# CMWC-Product.net
KiCad netlist of a schematic drawn in EAGLE
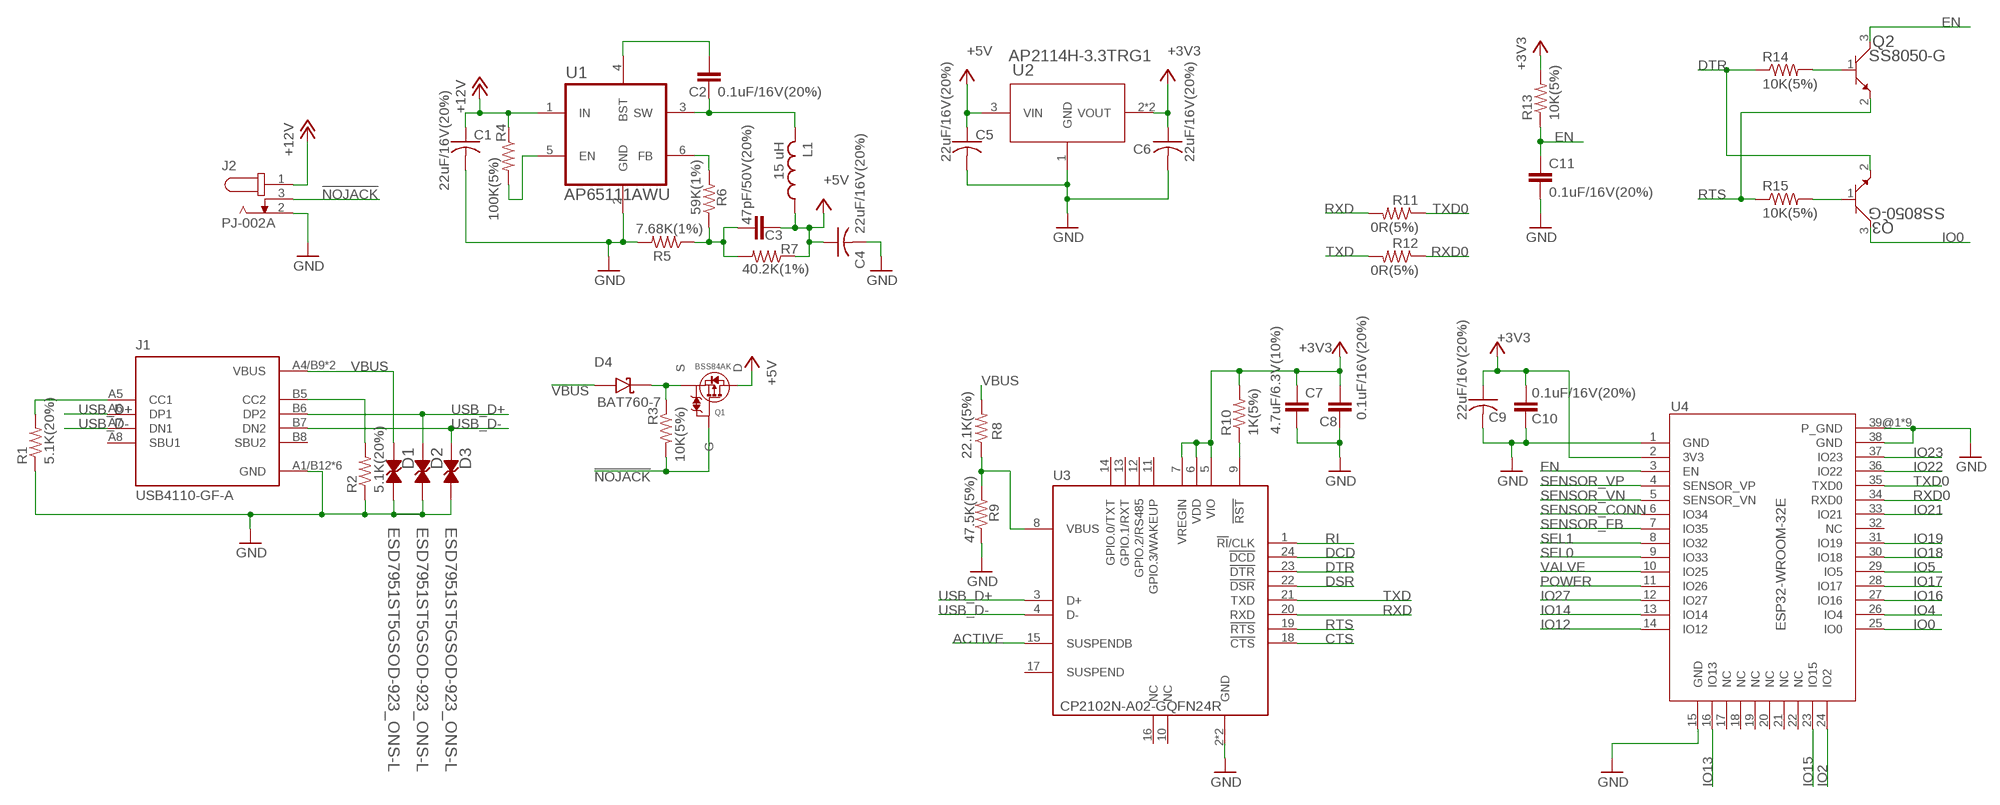
[diagram p0: schematic, sheet 1, part 1 of 2]
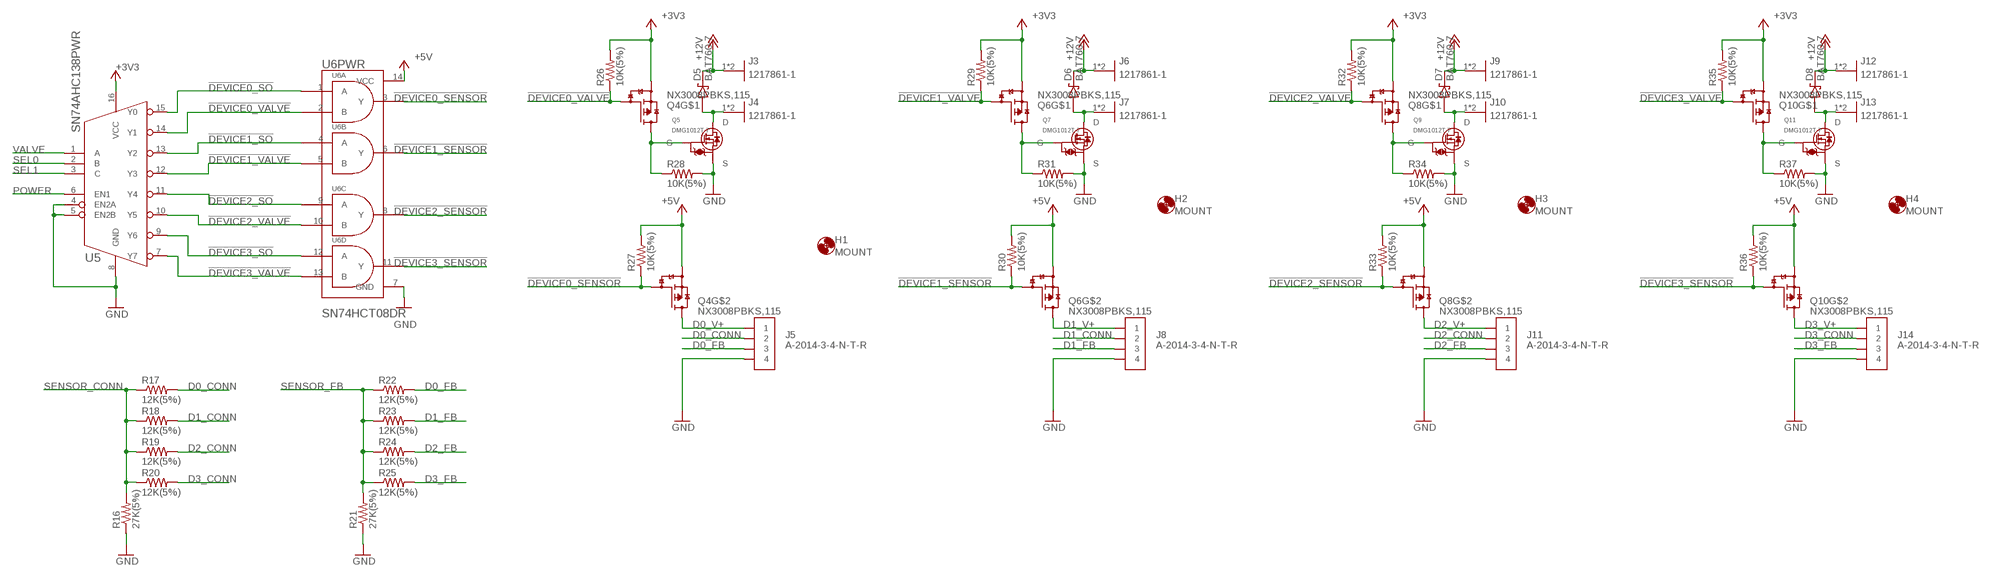
[diagram p1: schematic, sheet 1, part 2 of 2]

(export (version "E")
  (design (tool "Eeschema 10.0.6"))
  (components
    (comp (ref "C1")
      (value "22uF/16V(20%)")
      (footprint "eagle-import:C1206")
      (fields (field (name "DIGI-KEY_PART_NUMBER") "1276-2728-1-ND"))
      (libsource (lib "eagle-import") (part "C-USC1206"))
    )
    (comp (ref "C2")
      (value "0.1uF/16V(20%)")
      (footprint "eagle-import:C0603")
      (fields (field (name "DIGI-KEY_PART_NUMBER") "399-1099-1-ND"))
      (libsource (lib "eagle-import") (part "C-EUC0603"))
    )
    (comp (ref "C3")
      (value "47pF/50V(20%)")
      (footprint "eagle-import:C0603")
      (fields (field (name "DIGI-KEY_PART_NUMBER") "399-1099-1-ND"))
      (libsource (lib "eagle-import") (part "C-EUC0603"))
    )
    (comp (ref "C4")
      (value "22uF/16V(20%)")
      (footprint "eagle-import:C1206")
      (fields (field (name "DIGI-KEY_PART_NUMBER") "1276-2728-1-ND"))
      (libsource (lib "eagle-import") (part "C-USC1206"))
    )
    (comp (ref "C5")
      (value "22uF/16V(20%)")
      (footprint "eagle-import:C1206")
      (fields (field (name "DIGI-KEY_PART_NUMBER") "1276-2728-1-ND"))
      (libsource (lib "eagle-import") (part "C-USC1206"))
    )
    (comp (ref "C6")
      (value "22uF/16V(20%)")
      (footprint "eagle-import:C1206")
      (fields (field (name "DIGI-KEY_PART_NUMBER") "1276-2728-1-ND"))
      (libsource (lib "eagle-import") (part "C-USC1206"))
    )
    (comp (ref "C7")
      (value "4.7uF/6.3V(10%)")
      (footprint "eagle-import:C0603")
      (fields (field (name "DIGI-KEY_PART_NUMBER") "1276-1045-1-ND"))
      (libsource (lib "eagle-import") (part "C-EUC0603"))
    )
    (comp (ref "C8")
      (value "0.1uF/16V(20%)")
      (footprint "eagle-import:C0603")
      (fields (field (name "DIGI-KEY_PART_NUMBER") "399-1099-1-ND"))
      (libsource (lib "eagle-import") (part "C-EUC0603"))
    )
    (comp (ref "C9")
      (value "22uF/16V(20%)")
      (footprint "eagle-import:C1206")
      (fields (field (name "DIGI-KEY_PART_NUMBER") "1276-2728-1-ND"))
      (libsource (lib "eagle-import") (part "C-USC1206"))
    )
    (comp (ref "C10")
      (value "0.1uF/16V(20%)")
      (footprint "eagle-import:C0603")
      (fields (field (name "DIGI-KEY_PART_NUMBER") "399-1099-1-ND"))
      (libsource (lib "eagle-import") (part "C-EUC0603"))
    )
    (comp (ref "C11")
      (value "0.1uF/16V(20%)")
      (footprint "eagle-import:C0603")
      (fields (field (name "DIGI-KEY_PART_NUMBER") "399-1099-1-ND"))
      (libsource (lib "eagle-import") (part "C-EUC0603"))
    )
    (comp (ref "D1")
      (value "ESD7951ST5GSOD-923_ONS-L")
      (footprint "eagle-import:SOD-923_ONS-L")
      (fields
        (field (name "DIGI-KEY_PART_NUMBER") "ESD7951ST5GOSCT-ND")
        (field (name "MANUFACTURER_PART_NUMBER") "ESD7951ST5G")
        (field (name "COPYRIGHT") "Copyright (C) 2018 Accelerated Designs. All rights reserved")
      )
      (libsource (lib "eagle-import") (part "ESD7951ST5GSOD-923_ONS-L"))
    )
    (comp (ref "D2")
      (value "ESD7951ST5GSOD-923_ONS-L")
      (footprint "eagle-import:SOD-923_ONS-L")
      (fields
        (field (name "DIGI-KEY_PART_NUMBER") "ESD7951ST5GOSCT-ND")
        (field (name "MANUFACTURER_PART_NUMBER") "ESD7951ST5G")
        (field (name "COPYRIGHT") "Copyright (C) 2018 Accelerated Designs. All rights reserved")
      )
      (libsource (lib "eagle-import") (part "ESD7951ST5GSOD-923_ONS-L"))
    )
    (comp (ref "D3")
      (value "ESD7951ST5GSOD-923_ONS-L")
      (footprint "eagle-import:SOD-923_ONS-L")
      (fields
        (field (name "DIGI-KEY_PART_NUMBER") "ESD7951ST5GOSCT-ND")
        (field (name "MANUFACTURER_PART_NUMBER") "ESD7951ST5G")
        (field (name "COPYRIGHT") "Copyright (C) 2018 Accelerated Designs. All rights reserved")
      )
      (libsource (lib "eagle-import") (part "ESD7951ST5GSOD-923_ONS-L"))
    )
    (comp (ref "D4")
      (value "BAT760-7")
      (footprint "eagle-import:SOD2513X120N")
      (fields (field (name "DIGI-KEY_PART_NUMBER") "BAT760DICT-ND") (field (name "MF") "Diodes Inc."))
      (libsource (lib "eagle-import") (part "BAT760-7"))
    )
    (comp (ref "D5")
      (value "BAT760-7")
      (footprint "eagle-import:SOD2513X120N")
      (fields (field (name "DIGI-KEY_PART_NUMBER") "BAT760DICT-ND") (field (name "MF") "Diodes Inc."))
      (libsource (lib "eagle-import") (part "BAT760-7"))
    )
    (comp (ref "D6")
      (value "BAT760-7")
      (footprint "eagle-import:SOD2513X120N")
      (fields (field (name "DIGI-KEY_PART_NUMBER") "BAT760DICT-ND") (field (name "MF") "Diodes Inc."))
      (libsource (lib "eagle-import") (part "BAT760-7"))
    )
    (comp (ref "D7")
      (value "BAT760-7")
      (footprint "eagle-import:SOD2513X120N")
      (fields (field (name "DIGI-KEY_PART_NUMBER") "BAT760DICT-ND") (field (name "MF") "Diodes Inc."))
      (libsource (lib "eagle-import") (part "BAT760-7"))
    )
    (comp (ref "D8")
      (value "BAT760-7")
      (footprint "eagle-import:SOD2513X120N")
      (fields (field (name "DIGI-KEY_PART_NUMBER") "BAT760DICT-ND") (field (name "MF") "Diodes Inc."))
      (libsource (lib "eagle-import") (part "BAT760-7"))
    )
    (comp (ref "H1")
      (value "MOUNT")
      (footprint "eagle-import:#6-MOUNT")
      (libsource (lib "eagle-import") (part "MOUNT"))
    )
    (comp (ref "H2")
      (value "MOUNT")
      (footprint "eagle-import:#6-MOUNT")
      (libsource (lib "eagle-import") (part "MOUNT"))
    )
    (comp (ref "H3")
      (value "MOUNT")
      (footprint "eagle-import:#6-MOUNT")
      (libsource (lib "eagle-import") (part "MOUNT"))
    )
    (comp (ref "H4")
      (value "MOUNT")
      (footprint "eagle-import:#6-MOUNT")
      (libsource (lib "eagle-import") (part "MOUNT"))
    )
    (comp (ref "J1")
      (value "USB4110-GF-A")
      (footprint "eagle-import:GCT_USB4110-GF-A")
      (fields (field (name "DIGI-KEY_PART_NUMBER") "2073-USB4110-GF-A-1-ND") (field (name "MF") "GCT"))
      (libsource (lib "eagle-import") (part "USB4110-GF-A"))
    )
    (comp (ref "J2")
      (value "PJ-002A")
      (footprint "eagle-import:CUI_PJ-002A")
      (fields (field (name "DIGI-KEY_PART_NUMBER") "CP-002A-ND") (field (name "MF") "CUI Devices"))
      (libsource (lib "eagle-import") (part "PJ-002A"))
    )
    (comp (ref "J3")
      (value "1217861-1")
      (footprint "eagle-import:TE_1217861-1")
      (fields (field (name "DIGI-KEY_PART_NUMBER") "A100452CT-ND") (field (name "MF") "TE Connectivity"))
      (libsource (lib "eagle-import") (part "1217861-1"))
    )
    (comp (ref "J4")
      (value "1217861-1")
      (footprint "eagle-import:TE_1217861-1")
      (fields (field (name "DIGI-KEY_PART_NUMBER") "A100452CT-ND") (field (name "MF") "TE Connectivity"))
      (libsource (lib "eagle-import") (part "1217861-1"))
    )
    (comp (ref "J5")
      (value "A-2014-3-4-N-T-R")
      (footprint "eagle-import:A-2014-3-4-N-T-R")
      (fields (field (name "DIGI-KEY_PART_NUMBER") "AE10393-ND"))
      (libsource (lib "eagle-import") (part "A-2014-3-4-N-T-R"))
    )
    (comp (ref "J6")
      (value "1217861-1")
      (footprint "eagle-import:TE_1217861-1")
      (fields (field (name "DIGI-KEY_PART_NUMBER") "A100452CT-ND") (field (name "MF") "TE Connectivity"))
      (libsource (lib "eagle-import") (part "1217861-1"))
    )
    (comp (ref "J7")
      (value "1217861-1")
      (footprint "eagle-import:TE_1217861-1")
      (fields (field (name "DIGI-KEY_PART_NUMBER") "A100452CT-ND") (field (name "MF") "TE Connectivity"))
      (libsource (lib "eagle-import") (part "1217861-1"))
    )
    (comp (ref "J8")
      (value "A-2014-3-4-N-T-R")
      (footprint "eagle-import:A-2014-3-4-N-T-R")
      (fields (field (name "DIGI-KEY_PART_NUMBER") "AE10393-ND"))
      (libsource (lib "eagle-import") (part "A-2014-3-4-N-T-R"))
    )
    (comp (ref "J9")
      (value "1217861-1")
      (footprint "eagle-import:TE_1217861-1")
      (fields (field (name "DIGI-KEY_PART_NUMBER") "A100452CT-ND") (field (name "MF") "TE Connectivity"))
      (libsource (lib "eagle-import") (part "1217861-1"))
    )
    (comp (ref "J10")
      (value "1217861-1")
      (footprint "eagle-import:TE_1217861-1")
      (fields (field (name "DIGI-KEY_PART_NUMBER") "A100452CT-ND") (field (name "MF") "TE Connectivity"))
      (libsource (lib "eagle-import") (part "1217861-1"))
    )
    (comp (ref "J11")
      (value "A-2014-3-4-N-T-R")
      (footprint "eagle-import:A-2014-3-4-N-T-R")
      (fields (field (name "DIGI-KEY_PART_NUMBER") "AE10393-ND"))
      (libsource (lib "eagle-import") (part "A-2014-3-4-N-T-R"))
    )
    (comp (ref "J12")
      (value "1217861-1")
      (footprint "eagle-import:TE_1217861-1")
      (fields (field (name "DIGI-KEY_PART_NUMBER") "A100452CT-ND") (field (name "MF") "TE Connectivity"))
      (libsource (lib "eagle-import") (part "1217861-1"))
    )
    (comp (ref "J13")
      (value "1217861-1")
      (footprint "eagle-import:TE_1217861-1")
      (fields (field (name "DIGI-KEY_PART_NUMBER") "A100452CT-ND") (field (name "MF") "TE Connectivity"))
      (libsource (lib "eagle-import") (part "1217861-1"))
    )
    (comp (ref "J14")
      (value "A-2014-3-4-N-T-R")
      (footprint "eagle-import:A-2014-3-4-N-T-R")
      (fields (field (name "DIGI-KEY_PART_NUMBER") "AE10393-ND"))
      (libsource (lib "eagle-import") (part "A-2014-3-4-N-T-R"))
    )
    (comp (ref "L1")
      (value "15 uH")
      (footprint "eagle-import:BWVS00505040")
      (fields (field (name "DIGI-KEY_PART_NUMBER") "2184-BWVS00505040150M00CT-ND"))
      (libsource (lib "eagle-import") (part "BWVS00505040150M00"))
    )
    (comp (ref "Q1")
      (value "BSS84AK")
      (footprint "eagle-import:TO236")
      (fields (field (name "DIGI-KEY_PART_NUMBER") "1727-1144-1-ND"))
      (libsource (lib "eagle-import") (part "BSS84AK"))
    )
    (comp (ref "Q2")
      (value "SS8050-G")
      (footprint "eagle-import:TRAN_SS8050-G_CIP")
      (fields
        (field (name "DIGI-KEY_PART_NUMBER") "641-1790-1-ND")
        (field (name "COPYRIGHT") "Copyright (C) 2018 Accelerated Designs. All rights reserved")
      )
      (libsource (lib "eagle-import") (part "SS8050-G"))
    )
    (comp (ref "Q3")
      (value "SS8050-G")
      (footprint "eagle-import:TRAN_SS8050-G_CIP")
      (fields
        (field (name "DIGI-KEY_PART_NUMBER") "641-1790-1-ND")
        (field (name "COPYRIGHT") "Copyright (C) 2018 Accelerated Designs. All rights reserved")
      )
      (libsource (lib "eagle-import") (part "SS8050-G"))
    )
    (comp (ref "Q4")
      (value "NX3008PBKS,115")
      (footprint "eagle-import:SOT65P210X110-6N")
      (fields (field (name "DIGI-KEY_PART_NUMBER") "1727-1282-1-ND") (field (name "MF") "Nexperia USA"))
      (libsource (lib "eagle-import") (part "NX3008PBKS,115"))
    )
    (comp (ref "Q5")
      (value "DMG1012T-7")
      (footprint "eagle-import:SOT523")
      (fields (field (name "DIGI-KEY_PART_NUMBER") "DMG1012T-7DICT-ND"))
      (libsource (lib "eagle-import") (part "DMG1012T-7"))
    )
    (comp (ref "Q6")
      (value "NX3008PBKS,115")
      (footprint "eagle-import:SOT65P210X110-6N")
      (fields (field (name "DIGI-KEY_PART_NUMBER") "1727-1282-1-ND") (field (name "MF") "Nexperia USA"))
      (libsource (lib "eagle-import") (part "NX3008PBKS,115"))
    )
    (comp (ref "Q7")
      (value "DMG1012T-7")
      (footprint "eagle-import:SOT523")
      (fields (field (name "DIGI-KEY_PART_NUMBER") "DMG1012T-7DICT-ND"))
      (libsource (lib "eagle-import") (part "DMG1012T-7"))
    )
    (comp (ref "Q8")
      (value "NX3008PBKS,115")
      (footprint "eagle-import:SOT65P210X110-6N")
      (fields (field (name "DIGI-KEY_PART_NUMBER") "1727-1282-1-ND") (field (name "MF") "Nexperia USA"))
      (libsource (lib "eagle-import") (part "NX3008PBKS,115"))
    )
    (comp (ref "Q9")
      (value "DMG1012T-7")
      (footprint "eagle-import:SOT523")
      (fields (field (name "DIGI-KEY_PART_NUMBER") "DMG1012T-7DICT-ND"))
      (libsource (lib "eagle-import") (part "DMG1012T-7"))
    )
    (comp (ref "Q10")
      (value "NX3008PBKS,115")
      (footprint "eagle-import:SOT65P210X110-6N")
      (fields (field (name "DIGI-KEY_PART_NUMBER") "1727-1282-1-ND") (field (name "MF") "Nexperia USA"))
      (libsource (lib "eagle-import") (part "NX3008PBKS,115"))
    )
    (comp (ref "Q11")
      (value "DMG1012T-7")
      (footprint "eagle-import:SOT523")
      (fields (field (name "DIGI-KEY_PART_NUMBER") "DMG1012T-7DICT-ND"))
      (libsource (lib "eagle-import") (part "DMG1012T-7"))
    )
    (comp (ref "R1")
      (value "5.1K(20%)")
      (footprint "eagle-import:R0603")
      (fields (field (name "DIGI-KEY_PART_NUMBER") "RR08P5.1KDCT-ND"))
      (libsource (lib "eagle-import") (part "R-US_R0603"))
    )
    (comp (ref "R2")
      (value "5.1K(20%)")
      (footprint "eagle-import:R0603")
      (fields (field (name "DIGI-KEY_PART_NUMBER") "RR08P5.1KDCT-ND"))
      (libsource (lib "eagle-import") (part "R-US_R0603"))
    )
    (comp (ref "R3")
      (value "10K(5%)")
      (footprint "eagle-import:R0603")
      (fields (field (name "DIGI-KEY_PART_NUMBER") "RNCP0603FTD10K0CT-ND"))
      (libsource (lib "eagle-import") (part "R-US_R0603"))
    )
    (comp (ref "R4")
      (value "100K(5%)")
      (footprint "eagle-import:R0603")
      (fields (field (name "DIGI-KEY_PART_NUMBER") "RR08P100KDCT-ND"))
      (libsource (lib "eagle-import") (part "R-US_R0603"))
    )
    (comp (ref "R5")
      (value "7.68K(1%)")
      (footprint "eagle-import:R0603")
      (fields (field (name "DIGI-KEY_PART_NUMBER") "541-768HCT-ND"))
      (libsource (lib "eagle-import") (part "R-US_R0603"))
    )
    (comp (ref "R6")
      (value "59K(1%)")
      (footprint "eagle-import:R0603")
      (fields (field (name "DIGI-KEY_PART_NUMBER") "RMCF0603FT59K0CT-ND"))
      (libsource (lib "eagle-import") (part "R-US_R0603"))
    )
    (comp (ref "R7")
      (value "40.2K(1%)")
      (footprint "eagle-import:R0603")
      (fields (field (name "DIGI-KEY_PART_NUMBER") "CR0603-FX-4022ELFCT-ND"))
      (libsource (lib "eagle-import") (part "R-US_R0603"))
    )
    (comp (ref "R8")
      (value "22.1K(5%)")
      (footprint "eagle-import:R0603")
      (fields (field (name "DIGI-KEY_PART_NUMBER") "RR08P22.1KDCT-ND"))
      (libsource (lib "eagle-import") (part "R-US_R0603"))
    )
    (comp (ref "R9")
      (value "47.5K(5%)")
      (footprint "eagle-import:R0603")
      (fields (field (name "DIGI-KEY_PART_NUMBER") "RR08P47.5KDCT-ND"))
      (libsource (lib "eagle-import") (part "R-US_R0603"))
    )
    (comp (ref "R10")
      (value "1K(5%)")
      (footprint "eagle-import:R0603")
      (fields (field (name "DIGI-KEY_PART_NUMBER") "RR08P1.0KDCT-ND"))
      (libsource (lib "eagle-import") (part "R-US_R0603"))
    )
    (comp (ref "R11")
      (value "0R(5%)")
      (footprint "eagle-import:R0603")
      (fields (field (name "DIGI-KEY_PART_NUMBER") "CR0603-J/-000ELFCT-ND"))
      (libsource (lib "eagle-import") (part "R-US_R0603"))
    )
    (comp (ref "R12")
      (value "0R(5%)")
      (footprint "eagle-import:R0603")
      (fields (field (name "DIGI-KEY_PART_NUMBER") "CR0603-J/-000ELFCT-ND"))
      (libsource (lib "eagle-import") (part "R-US_R0603"))
    )
    (comp (ref "R13")
      (value "10K(5%)")
      (footprint "eagle-import:R0603")
      (fields (field (name "DIGI-KEY_PART_NUMBER") "RNCP0603FTD10K0CT-ND"))
      (libsource (lib "eagle-import") (part "R-US_R0603"))
    )
    (comp (ref "R14")
      (value "10K(5%)")
      (footprint "eagle-import:R0603")
      (fields (field (name "DIGI-KEY_PART_NUMBER") "RNCP0603FTD10K0CT-ND"))
      (libsource (lib "eagle-import") (part "R-US_R0603"))
    )
    (comp (ref "R15")
      (value "10K(5%)")
      (footprint "eagle-import:R0603")
      (fields (field (name "DIGI-KEY_PART_NUMBER") "RNCP0603FTD10K0CT-ND"))
      (libsource (lib "eagle-import") (part "R-US_R0603"))
    )
    (comp (ref "R16")
      (value "27K(5%)")
      (footprint "eagle-import:R0603")
      (fields (field (name "DIGI-KEY_PART_NUMBER") "541-27.0KHCT-ND"))
      (libsource (lib "eagle-import") (part "R-US_R0603"))
    )
    (comp (ref "R17")
      (value "12K(5%)")
      (footprint "eagle-import:R0603")
      (fields (field (name "DIGI-KEY_PART_NUMBER") "311-2415-1-ND"))
      (libsource (lib "eagle-import") (part "R-US_R0603"))
    )
    (comp (ref "R18")
      (value "12K(5%)")
      (footprint "eagle-import:R0603")
      (fields (field (name "DIGI-KEY_PART_NUMBER") "311-2415-1-ND"))
      (libsource (lib "eagle-import") (part "R-US_R0603"))
    )
    (comp (ref "R19")
      (value "12K(5%)")
      (footprint "eagle-import:R0603")
      (fields (field (name "DIGI-KEY_PART_NUMBER") "311-2415-1-ND"))
      (libsource (lib "eagle-import") (part "R-US_R0603"))
    )
    (comp (ref "R20")
      (value "12K(5%)")
      (footprint "eagle-import:R0603")
      (fields (field (name "DIGI-KEY_PART_NUMBER") "311-2415-1-ND"))
      (libsource (lib "eagle-import") (part "R-US_R0603"))
    )
    (comp (ref "R21")
      (value "27K(5%)")
      (footprint "eagle-import:R0603")
      (fields (field (name "DIGI-KEY_PART_NUMBER") "541-27.0KHCT-ND"))
      (libsource (lib "eagle-import") (part "R-US_R0603"))
    )
    (comp (ref "R22")
      (value "12K(5%)")
      (footprint "eagle-import:R0603")
      (fields (field (name "DIGI-KEY_PART_NUMBER") "311-2415-1-ND"))
      (libsource (lib "eagle-import") (part "R-US_R0603"))
    )
    (comp (ref "R23")
      (value "12K(5%)")
      (footprint "eagle-import:R0603")
      (fields (field (name "DIGI-KEY_PART_NUMBER") "311-2415-1-ND"))
      (libsource (lib "eagle-import") (part "R-US_R0603"))
    )
    (comp (ref "R24")
      (value "12K(5%)")
      (footprint "eagle-import:R0603")
      (fields (field (name "DIGI-KEY_PART_NUMBER") "311-2415-1-ND"))
      (libsource (lib "eagle-import") (part "R-US_R0603"))
    )
    (comp (ref "R25")
      (value "12K(5%)")
      (footprint "eagle-import:R0603")
      (fields (field (name "DIGI-KEY_PART_NUMBER") "311-2415-1-ND"))
      (libsource (lib "eagle-import") (part "R-US_R0603"))
    )
    (comp (ref "R26")
      (value "10K(5%)")
      (footprint "eagle-import:R0603")
      (fields (field (name "DIGI-KEY_PART_NUMBER") "RNCP0603FTD10K0CT-ND"))
      (libsource (lib "eagle-import") (part "R-US_R0603"))
    )
    (comp (ref "R27")
      (value "10K(5%)")
      (footprint "eagle-import:R0603")
      (fields (field (name "DIGI-KEY_PART_NUMBER") "RNCP0603FTD10K0CT-ND"))
      (libsource (lib "eagle-import") (part "R-US_R0603"))
    )
    (comp (ref "R28")
      (value "10K(5%)")
      (footprint "eagle-import:R0603")
      (fields (field (name "DIGI-KEY_PART_NUMBER") "RNCP0603FTD10K0CT-ND"))
      (libsource (lib "eagle-import") (part "R-US_R0603"))
    )
    (comp (ref "R29")
      (value "10K(5%)")
      (footprint "eagle-import:R0603")
      (fields (field (name "DIGI-KEY_PART_NUMBER") "RNCP0603FTD10K0CT-ND"))
      (libsource (lib "eagle-import") (part "R-US_R0603"))
    )
    (comp (ref "R30")
      (value "10K(5%)")
      (footprint "eagle-import:R0603")
      (fields (field (name "DIGI-KEY_PART_NUMBER") "RNCP0603FTD10K0CT-ND"))
      (libsource (lib "eagle-import") (part "R-US_R0603"))
    )
    (comp (ref "R31")
      (value "10K(5%)")
      (footprint "eagle-import:R0603")
      (fields (field (name "DIGI-KEY_PART_NUMBER") "RNCP0603FTD10K0CT-ND"))
      (libsource (lib "eagle-import") (part "R-US_R0603"))
    )
    (comp (ref "R32")
      (value "10K(5%)")
      (footprint "eagle-import:R0603")
      (fields (field (name "DIGI-KEY_PART_NUMBER") "RNCP0603FTD10K0CT-ND"))
      (libsource (lib "eagle-import") (part "R-US_R0603"))
    )
    (comp (ref "R33")
      (value "10K(5%)")
      (footprint "eagle-import:R0603")
      (fields (field (name "DIGI-KEY_PART_NUMBER") "RNCP0603FTD10K0CT-ND"))
      (libsource (lib "eagle-import") (part "R-US_R0603"))
    )
    (comp (ref "R34")
      (value "10K(5%)")
      (footprint "eagle-import:R0603")
      (fields (field (name "DIGI-KEY_PART_NUMBER") "RNCP0603FTD10K0CT-ND"))
      (libsource (lib "eagle-import") (part "R-US_R0603"))
    )
    (comp (ref "R35")
      (value "10K(5%)")
      (footprint "eagle-import:R0603")
      (fields (field (name "DIGI-KEY_PART_NUMBER") "RNCP0603FTD10K0CT-ND"))
      (libsource (lib "eagle-import") (part "R-US_R0603"))
    )
    (comp (ref "R36")
      (value "10K(5%)")
      (footprint "eagle-import:R0603")
      (fields (field (name "DIGI-KEY_PART_NUMBER") "RNCP0603FTD10K0CT-ND"))
      (libsource (lib "eagle-import") (part "R-US_R0603"))
    )
    (comp (ref "R37")
      (value "10K(5%)")
      (footprint "eagle-import:R0603")
      (fields (field (name "DIGI-KEY_PART_NUMBER") "RNCP0603FTD10K0CT-ND"))
      (libsource (lib "eagle-import") (part "R-US_R0603"))
    )
    (comp (ref "U1")
      (value "AP65111AWU")
      (footprint "eagle-import:SOT95P280X100-6N")
      (fields
        (field (name "DIGI-KEY_PART_NUMBER") "AP65111AWU-7DICT-ND")
        (field (name "MF") "Diodes Inc.")
        (field (name "MP") "AP65111AWU-7")
      )
      (libsource (lib "eagle-import") (part "AP65111AWU-7"))
    )
    (comp (ref "U2")
      (value "AP2114H-3.3TRG1")
      (footprint "eagle-import:SOT-223_DIO")
      (fields (field (name "DIGI-KEY_PART_NUMBER") "AP2114H-3.3TRG1DICT-ND"))
      (libsource (lib "eagle-import") (part "AP2114H-3.3TRG1"))
    )
    (comp (ref "U3")
      (value "CP2102N-A02-GQFN24R")
      (footprint "eagle-import:QFN50P400X400X80-25N")
      (fields (field (name "DIGI-KEY_PART_NUMBER") "336-5888-1-ND") (field (name "MF") "Silicon Labs"))
      (libsource (lib "eagle-import") (part "CP2102N-A02-GQFN24R"))
    )
    (comp (ref "U4")
      (value "ESP32-WROOM-32E")
      (footprint "eagle-import:ESP32-WROOM-32E")
      (fields (field (name "DIGI-KEY_PART_NUMBER") "1965-ESP32-WROOM-32E(4MB)CT-ND"))
      (libsource (lib "eagle-import") (part "ESP32-WROOM-32E"))
    )
    (comp (ref "U5")
      (value "SN74AHC138PWR")
      (footprint "eagle-import:SOP65P640X120-16N")
      (fields (field (name "DIGI-KEY_PART_NUMBER") "296-1084-1-ND") (field (name "MF") "Texas Instruments"))
      (libsource (lib "eagle-import") (part "SN74AHC138PWR"))
    )
    (comp (ref "U6")
      (value "SN74HCT08DR")
      (footprint "eagle-import:SOIC127P600X175-14N")
      (fields (field (name "DIGI-KEY_PART_NUMBER") "296-14862-1-ND") (field (name "MF") "Texas Instruments"))
      (libsource (lib "eagle-import") (part "SN74HCT08DR"))
    )
  )
  (nets
    (net (code "1") (name "+3V3") (class "Default")
      (node (ref "C10") (pin "1") (pinfunction "1_1") (pintype "passive"))
      (node (ref "C6") (pin "1") (pinfunction "1_1") (pintype "passive"))
      (node (ref "C7") (pin "1") (pinfunction "1_1") (pintype "passive"))
      (node (ref "C8") (pin "1") (pinfunction "1_1") (pintype "passive"))
      (node (ref "C9") (pin "1") (pinfunction "1_1") (pintype "passive"))
      (node (ref "Q10") (pin "1") (pinfunction "S1_1") (pintype "passive"))
      (node (ref "Q4") (pin "1") (pinfunction "S1_1") (pintype "passive"))
      (node (ref "Q6") (pin "1") (pinfunction "S1_1") (pintype "passive"))
      (node (ref "Q8") (pin "1") (pinfunction "S1_1") (pintype "passive"))
      (node (ref "R10") (pin "2") (pinfunction "2_2") (pintype "passive"))
      (node (ref "R13") (pin "2") (pinfunction "2_2") (pintype "passive"))
      (node (ref "R26") (pin "2") (pinfunction "2_2") (pintype "passive"))
      (node (ref "R29") (pin "2") (pinfunction "2_2") (pintype "passive"))
      (node (ref "R32") (pin "2") (pinfunction "2_2") (pintype "passive"))
      (node (ref "R35") (pin "2") (pinfunction "2_2") (pintype "passive"))
      (node (ref "U2") (pin "2") (pinfunction "VOUT_2") (pintype "power_in"))
      (node (ref "U2") (pin "4") (pinfunction "VOUT_4") (pintype "power_in"))
      (node (ref "U3") (pin "5") (pinfunction "VIO_5") (pintype "power_in"))
      (node (ref "U3") (pin "6") (pinfunction "VDD_6") (pintype "power_in"))
      (node (ref "U3") (pin "7") (pinfunction "VREGIN_7") (pintype "input"))
      (node (ref "U4") (pin "2") (pinfunction "3V3_2") (pintype "power_in"))
      (node (ref "U5") (pin "16") (pinfunction "VCC_16") (pintype "power_in"))
    )
    (net (code "2") (name "+5V") (class "Default")
      (node (ref "C3") (pin "2") (pinfunction "2_2") (pintype "passive"))
      (node (ref "C4") (pin "1") (pinfunction "1_1") (pintype "passive"))
      (node (ref "C5") (pin "1") (pinfunction "1_1") (pintype "passive"))
      (node (ref "L1") (pin "P$1") (pinfunction "1_P$1") (pintype "passive"))
      (node (ref "Q1") (pin "D") (pinfunction "D_D") (pintype "bidirectional"))
      (node (ref "Q10") (pin "4") (pinfunction "S2_4") (pintype "passive"))
      (node (ref "Q4") (pin "4") (pinfunction "S2_4") (pintype "passive"))
      (node (ref "Q6") (pin "4") (pinfunction "S2_4") (pintype "passive"))
      (node (ref "Q8") (pin "4") (pinfunction "S2_4") (pintype "passive"))
      (node (ref "R27") (pin "2") (pinfunction "2_2") (pintype "passive"))
      (node (ref "R30") (pin "2") (pinfunction "2_2") (pintype "passive"))
      (node (ref "R33") (pin "2") (pinfunction "2_2") (pintype "passive"))
      (node (ref "R36") (pin "2") (pinfunction "2_2") (pintype "passive"))
      (node (ref "R7") (pin "1") (pinfunction "1_1") (pintype "passive"))
      (node (ref "U2") (pin "3") (pinfunction "VIN_3") (pintype "power_in"))
      (node (ref "U6") (pin "14") (pinfunction "VCC_14") (pintype "bidirectional"))
    )
    (net (code "3") (name "+12V") (class "Default")
      (node (ref "C1") (pin "1") (pinfunction "1_1") (pintype "passive"))
      (node (ref "D5") (pin "C") (pinfunction "C_C") (pintype "passive"))
      (node (ref "D6") (pin "C") (pinfunction "C_C") (pintype "passive"))
      (node (ref "D7") (pin "C") (pinfunction "C_C") (pintype "passive"))
      (node (ref "D8") (pin "C") (pinfunction "C_C") (pintype "passive"))
      (node (ref "J12") (pin "1") (pinfunction "1_1") (pintype "passive"))
      (node (ref "J12") (pin "2") (pinfunction "1_2") (pintype "passive"))
      (node (ref "J2") (pin "1") (pinfunction "1_1") (pintype "passive"))
      (node (ref "J3") (pin "1") (pinfunction "1_1") (pintype "passive"))
      (node (ref "J3") (pin "2") (pinfunction "1_2") (pintype "passive"))
      (node (ref "J6") (pin "1") (pinfunction "1_1") (pintype "passive"))
      (node (ref "J6") (pin "2") (pinfunction "1_2") (pintype "passive"))
      (node (ref "J9") (pin "1") (pinfunction "1_1") (pintype "passive"))
      (node (ref "J9") (pin "2") (pinfunction "1_2") (pintype "passive"))
      (node (ref "R4") (pin "1") (pinfunction "1_1") (pintype "passive"))
      (node (ref "U1") (pin "1") (pinfunction "IN_1") (pintype "input"))
    )
    (net (code "4") (name "/ACTIVE") (class "Default")
      (node (ref "U3") (pin "15") (pinfunction "SUSPENDB_15") (pintype "output"))
    )
    (net (code "5") (name "/CTS") (class "Default")
      (node (ref "U3") (pin "18") (pinfunction "~{CTS}_18") (pintype "input"))
    )
    (net (code "6") (name "/D0_CONN") (class "Default")
      (node (ref "J5") (pin "2") (pinfunction "2_2") (pintype "bidirectional"))
      (node (ref "R17") (pin "2") (pinfunction "2_2") (pintype "passive"))
    )
    (net (code "7") (name "/D0_FB") (class "Default")
      (node (ref "J5") (pin "3") (pinfunction "3_3") (pintype "bidirectional"))
      (node (ref "R22") (pin "2") (pinfunction "2_2") (pintype "passive"))
    )
    (net (code "8") (name "/D0_V+") (class "Default")
      (node (ref "J5") (pin "1") (pinfunction "1_1") (pintype "bidirectional"))
      (node (ref "Q4") (pin "3") (pinfunction "D2_3") (pintype "passive"))
    )
    (net (code "9") (name "/D1_CONN") (class "Default")
      (node (ref "J8") (pin "2") (pinfunction "2_2") (pintype "bidirectional"))
      (node (ref "R18") (pin "2") (pinfunction "2_2") (pintype "passive"))
    )
    (net (code "10") (name "/D1_FB") (class "Default")
      (node (ref "J8") (pin "3") (pinfunction "3_3") (pintype "bidirectional"))
      (node (ref "R23") (pin "2") (pinfunction "2_2") (pintype "passive"))
    )
    (net (code "11") (name "/D1_V+") (class "Default")
      (node (ref "J8") (pin "1") (pinfunction "1_1") (pintype "bidirectional"))
      (node (ref "Q6") (pin "3") (pinfunction "D2_3") (pintype "passive"))
    )
    (net (code "12") (name "/D2_CONN") (class "Default")
      (node (ref "J11") (pin "2") (pinfunction "2_2") (pintype "bidirectional"))
      (node (ref "R19") (pin "2") (pinfunction "2_2") (pintype "passive"))
    )
    (net (code "13") (name "/D2_FB") (class "Default")
      (node (ref "J11") (pin "3") (pinfunction "3_3") (pintype "bidirectional"))
      (node (ref "R24") (pin "2") (pinfunction "2_2") (pintype "passive"))
    )
    (net (code "14") (name "/D2_V+") (class "Default")
      (node (ref "J11") (pin "1") (pinfunction "1_1") (pintype "bidirectional"))
      (node (ref "Q8") (pin "3") (pinfunction "D2_3") (pintype "passive"))
    )
    (net (code "15") (name "/D3_CONN") (class "Default")
      (node (ref "J14") (pin "2") (pinfunction "2_2") (pintype "bidirectional"))
      (node (ref "R20") (pin "2") (pinfunction "2_2") (pintype "passive"))
    )
    (net (code "16") (name "/D3_FB") (class "Default")
      (node (ref "J14") (pin "3") (pinfunction "3_3") (pintype "bidirectional"))
      (node (ref "R25") (pin "2") (pinfunction "2_2") (pintype "passive"))
    )
    (net (code "17") (name "/D3_V+") (class "Default")
      (node (ref "J14") (pin "1") (pinfunction "1_1") (pintype "bidirectional"))
      (node (ref "Q10") (pin "3") (pinfunction "D2_3") (pintype "passive"))
    )
    (net (code "18") (name "/DCD") (class "Default")
      (node (ref "U3") (pin "24") (pinfunction "~{DCD}_24") (pintype "input"))
    )
    (net (code "19") (name "/DSR") (class "Default")
      (node (ref "U3") (pin "22") (pinfunction "~{DSR}_22") (pintype "input"))
    )
    (net (code "20") (name "/DTR") (class "Default")
      (node (ref "Q3") (pin "2") (pinfunction "2_2") (pintype "passive"))
      (node (ref "R14") (pin "1") (pinfunction "1_1") (pintype "passive"))
      (node (ref "U3") (pin "23") (pinfunction "~{DTR}_23") (pintype "output"))
    )
    (net (code "21") (name "/EN") (class "Default")
      (node (ref "C11") (pin "1") (pinfunction "1_1") (pintype "passive"))
      (node (ref "Q2") (pin "3") (pinfunction "3_3") (pintype "passive"))
      (node (ref "R13") (pin "1") (pinfunction "1_1") (pintype "passive"))
      (node (ref "U4") (pin "3") (pinfunction "EN_3") (pintype "input"))
    )
    (net (code "22") (name "/IO0") (class "Default")
      (node (ref "Q3") (pin "3") (pinfunction "3_3") (pintype "passive"))
      (node (ref "U4") (pin "25") (pinfunction "IO0_25") (pintype "bidirectional"))
    )
    (net (code "23") (name "/IO2") (class "Default")
      (node (ref "U4") (pin "24") (pinfunction "IO2_24") (pintype "bidirectional"))
    )
    (net (code "24") (name "/IO4") (class "Default")
      (node (ref "U4") (pin "26") (pinfunction "IO4_26") (pintype "bidirectional"))
    )
    (net (code "25") (name "/IO5") (class "Default")
      (node (ref "U4") (pin "29") (pinfunction "IO5_29") (pintype "bidirectional"))
    )
    (net (code "26") (name "/IO12") (class "Default")
      (node (ref "U4") (pin "14") (pinfunction "IO12_14") (pintype "bidirectional"))
    )
    (net (code "27") (name "/IO13") (class "Default")
      (node (ref "U4") (pin "16") (pinfunction "IO13_16") (pintype "bidirectional"))
    )
    (net (code "28") (name "/IO14") (class "Default")
      (node (ref "U4") (pin "13") (pinfunction "IO14_13") (pintype "bidirectional"))
    )
    (net (code "29") (name "/IO15") (class "Default")
      (node (ref "U4") (pin "23") (pinfunction "IO15_23") (pintype "bidirectional"))
    )
    (net (code "30") (name "/IO16") (class "Default")
      (node (ref "U4") (pin "27") (pinfunction "IO16_27") (pintype "bidirectional"))
    )
    (net (code "31") (name "/IO17") (class "Default")
      (node (ref "U4") (pin "28") (pinfunction "IO17_28") (pintype "bidirectional"))
    )
    (net (code "32") (name "/IO18") (class "Default")
      (node (ref "U4") (pin "30") (pinfunction "IO18_30") (pintype "bidirectional"))
    )
    (net (code "33") (name "/IO19") (class "Default")
      (node (ref "U4") (pin "31") (pinfunction "IO19_31") (pintype "bidirectional"))
    )
    (net (code "34") (name "/IO21") (class "Default")
      (node (ref "U4") (pin "33") (pinfunction "IO21_33") (pintype "bidirectional"))
    )
    (net (code "35") (name "/IO22") (class "Default")
      (node (ref "U4") (pin "36") (pinfunction "IO22_36") (pintype "bidirectional"))
    )
    (net (code "36") (name "/IO23") (class "Default")
      (node (ref "U4") (pin "37") (pinfunction "IO23_37") (pintype "bidirectional"))
    )
    (net (code "37") (name "/IO27") (class "Default")
      (node (ref "U4") (pin "12") (pinfunction "IO27_12") (pintype "bidirectional"))
    )
    (net (code "38") (name "/POWER") (class "Default")
      (node (ref "U4") (pin "11") (pinfunction "IO26_11") (pintype "bidirectional"))
      (node (ref "U5") (pin "6") (pinfunction "EN1_6") (pintype "input"))
    )
    (net (code "39") (name "/RI") (class "Default")
      (node (ref "U3") (pin "1") (pinfunction "~{RI}/CLK_1") (pintype "bidirectional"))
    )
    (net (code "40") (name "/RTS") (class "Default")
      (node (ref "Q2") (pin "2") (pinfunction "2_2") (pintype "passive"))
      (node (ref "R15") (pin "1") (pinfunction "1_1") (pintype "passive"))
      (node (ref "U3") (pin "19") (pinfunction "~{RTS}_19") (pintype "output"))
    )
    (net (code "41") (name "/RXD") (class "Default")
      (node (ref "R11") (pin "2") (pinfunction "2_2") (pintype "passive"))
      (node (ref "U3") (pin "20") (pinfunction "RXD_20") (pintype "input"))
    )
    (net (code "42") (name "/RXD0") (class "Default")
      (node (ref "R12") (pin "1") (pinfunction "1_1") (pintype "passive"))
      (node (ref "U4") (pin "34") (pinfunction "RXD0_34") (pintype "bidirectional"))
    )
    (net (code "43") (name "/SEL0") (class "Default")
      (node (ref "U4") (pin "9") (pinfunction "IO33_9") (pintype "bidirectional"))
      (node (ref "U5") (pin "2") (pinfunction "B_2") (pintype "input"))
    )
    (net (code "44") (name "/SEL1") (class "Default")
      (node (ref "U4") (pin "8") (pinfunction "IO32_8") (pintype "bidirectional"))
      (node (ref "U5") (pin "3") (pinfunction "C_3") (pintype "input"))
    )
    (net (code "45") (name "/SENSOR_CONN") (class "Default")
      (node (ref "R16") (pin "2") (pinfunction "2_2") (pintype "passive"))
      (node (ref "R17") (pin "1") (pinfunction "1_1") (pintype "passive"))
      (node (ref "R18") (pin "1") (pinfunction "1_1") (pintype "passive"))
      (node (ref "R19") (pin "1") (pinfunction "1_1") (pintype "passive"))
      (node (ref "R20") (pin "1") (pinfunction "1_1") (pintype "passive"))
      (node (ref "U4") (pin "6") (pinfunction "IO34_6") (pintype "input"))
    )
    (net (code "46") (name "/SENSOR_FB") (class "Default")
      (node (ref "R21") (pin "2") (pinfunction "2_2") (pintype "passive"))
      (node (ref "R22") (pin "1") (pinfunction "1_1") (pintype "passive"))
      (node (ref "R23") (pin "1") (pinfunction "1_1") (pintype "passive"))
      (node (ref "R24") (pin "1") (pinfunction "1_1") (pintype "passive"))
      (node (ref "R25") (pin "1") (pinfunction "1_1") (pintype "passive"))
      (node (ref "U4") (pin "7") (pinfunction "IO35_7") (pintype "input"))
    )
    (net (code "47") (name "/SENSOR_VN") (class "Default")
      (node (ref "U4") (pin "5") (pinfunction "SENSOR_VN_5") (pintype "input"))
    )
    (net (code "48") (name "/SENSOR_VP") (class "Default")
      (node (ref "U4") (pin "4") (pinfunction "SENSOR_VP_4") (pintype "input"))
    )
    (net (code "49") (name "/TXD") (class "Default")
      (node (ref "R12") (pin "2") (pinfunction "2_2") (pintype "passive"))
      (node (ref "U3") (pin "21") (pinfunction "TXD_21") (pintype "output"))
    )
    (net (code "50") (name "/TXD0") (class "Default")
      (node (ref "R11") (pin "1") (pinfunction "1_1") (pintype "passive"))
      (node (ref "U4") (pin "35") (pinfunction "TXD0_35") (pintype "bidirectional"))
    )
    (net (code "51") (name "/USB_D+") (class "Default")
      (node (ref "D2") (pin "2") (pinfunction "ANODE_2") (pintype "passive"))
      (node (ref "J1") (pin "A6") (pinfunction "DP1_A6") (pintype "bidirectional"))
      (node (ref "J1") (pin "B6") (pinfunction "DP2_B6") (pintype "bidirectional"))
      (node (ref "U3") (pin "3") (pinfunction "D+_3") (pintype "bidirectional"))
    )
    (net (code "52") (name "/USB_D-") (class "Default")
      (node (ref "D3") (pin "2") (pinfunction "ANODE_2") (pintype "passive"))
      (node (ref "J1") (pin "A7") (pinfunction "DN1_A7") (pintype "bidirectional"))
      (node (ref "J1") (pin "B7") (pinfunction "DN2_B7") (pintype "bidirectional"))
      (node (ref "U3") (pin "4") (pinfunction "D-_4") (pintype "bidirectional"))
    )
    (net (code "53") (name "/VALVE") (class "Default")
      (node (ref "U4") (pin "10") (pinfunction "IO25_10") (pintype "bidirectional"))
      (node (ref "U5") (pin "1") (pinfunction "A_1") (pintype "input"))
    )
    (net (code "54") (name "/VBUS") (class "Default")
      (node (ref "D1") (pin "2") (pinfunction "ANODE_2") (pintype "passive"))
      (node (ref "D4") (pin "A") (pinfunction "A_A") (pintype "passive"))
      (node (ref "J1") (pin "A4/B9") (pinfunction "VBUS_A4/B9") (pintype "power_in"))
      (node (ref "J1") (pin "B4/A9") (pinfunction "VBUS_B4/A9") (pintype "power_in"))
      (node (ref "R8") (pin "2") (pinfunction "2_2") (pintype "passive"))
    )
    (net (code "55") (name "/~{DEVICE0_SENSOR}") (class "Default")
      (node (ref "Q4") (pin "5") (pinfunction "G2_5") (pintype "passive"))
      (node (ref "R27") (pin "1") (pinfunction "1_1") (pintype "passive"))
      (node (ref "U6") (pin "3") (pinfunction "Y_3") (pintype "output"))
    )
    (net (code "56") (name "/~{DEVICE0_SO}") (class "Default")
      (node (ref "U5") (pin "15") (pinfunction "Y0_15") (pintype "output"))
      (node (ref "U6") (pin "1") (pinfunction "A_1") (pintype "input"))
    )
    (net (code "57") (name "/~{DEVICE0_VALVE}") (class "Default")
      (node (ref "Q4") (pin "2") (pinfunction "G1_2") (pintype "passive"))
      (node (ref "R26") (pin "1") (pinfunction "1_1") (pintype "passive"))
      (node (ref "U5") (pin "14") (pinfunction "Y1_14") (pintype "output"))
      (node (ref "U6") (pin "2") (pinfunction "B_2") (pintype "input"))
    )
    (net (code "58") (name "/~{DEVICE1_SENSOR}") (class "Default")
      (node (ref "Q6") (pin "5") (pinfunction "G2_5") (pintype "passive"))
      (node (ref "R30") (pin "1") (pinfunction "1_1") (pintype "passive"))
      (node (ref "U6") (pin "6") (pinfunction "Y_6") (pintype "output"))
    )
    (net (code "59") (name "/~{DEVICE1_SO}") (class "Default")
      (node (ref "U5") (pin "13") (pinfunction "Y2_13") (pintype "output"))
      (node (ref "U6") (pin "4") (pinfunction "A_4") (pintype "input"))
    )
    (net (code "60") (name "/~{DEVICE1_VALVE}") (class "Default")
      (node (ref "Q6") (pin "2") (pinfunction "G1_2") (pintype "passive"))
      (node (ref "R29") (pin "1") (pinfunction "1_1") (pintype "passive"))
      (node (ref "U5") (pin "12") (pinfunction "Y3_12") (pintype "output"))
      (node (ref "U6") (pin "5") (pinfunction "B_5") (pintype "input"))
    )
    (net (code "61") (name "/~{DEVICE2_SENSOR}") (class "Default")
      (node (ref "Q8") (pin "5") (pinfunction "G2_5") (pintype "passive"))
      (node (ref "R33") (pin "1") (pinfunction "1_1") (pintype "passive"))
      (node (ref "U6") (pin "8") (pinfunction "Y_8") (pintype "output"))
    )
    (net (code "62") (name "/~{DEVICE2_SO}") (class "Default")
      (node (ref "U5") (pin "11") (pinfunction "Y4_11") (pintype "output"))
      (node (ref "U6") (pin "9") (pinfunction "A_9") (pintype "input"))
    )
    (net (code "63") (name "/~{DEVICE2_VALVE}") (class "Default")
      (node (ref "Q8") (pin "2") (pinfunction "G1_2") (pintype "passive"))
      (node (ref "R32") (pin "1") (pinfunction "1_1") (pintype "passive"))
      (node (ref "U5") (pin "10") (pinfunction "Y5_10") (pintype "output"))
      (node (ref "U6") (pin "10") (pinfunction "B_10") (pintype "input"))
    )
    (net (code "64") (name "/~{DEVICE3_SENSOR}") (class "Default")
      (node (ref "Q10") (pin "5") (pinfunction "G2_5") (pintype "passive"))
      (node (ref "R36") (pin "1") (pinfunction "1_1") (pintype "passive"))
      (node (ref "U6") (pin "11") (pinfunction "Y_11") (pintype "output"))
    )
    (net (code "65") (name "/~{DEVICE3_SO}") (class "Default")
      (node (ref "U5") (pin "9") (pinfunction "Y6_9") (pintype "output"))
      (node (ref "U6") (pin "12") (pinfunction "A_12") (pintype "input"))
    )
    (net (code "66") (name "/~{DEVICE3_VALVE}") (class "Default")
      (node (ref "Q10") (pin "2") (pinfunction "G1_2") (pintype "passive"))
      (node (ref "R35") (pin "1") (pinfunction "1_1") (pintype "passive"))
      (node (ref "U5") (pin "7") (pinfunction "Y7_7") (pintype "output"))
      (node (ref "U6") (pin "13") (pinfunction "B_13") (pintype "input"))
    )
    (net (code "67") (name "/~{NOJACK}") (class "Default")
      (node (ref "J2") (pin "3") (pinfunction "3_3") (pintype "passive"))
      (node (ref "Q1") (pin "G") (pinfunction "G_G") (pintype "bidirectional"))
      (node (ref "R3") (pin "2") (pinfunction "2_2") (pintype "passive"))
    )
    (net (code "68") (name "GND") (class "Default")
      (node (ref "C1") (pin "2") (pinfunction "2_2") (pintype "passive"))
      (node (ref "C10") (pin "2") (pinfunction "2_2") (pintype "passive"))
      (node (ref "C11") (pin "2") (pinfunction "2_2") (pintype "passive"))
      (node (ref "C4") (pin "2") (pinfunction "2_2") (pintype "passive"))
      (node (ref "C5") (pin "2") (pinfunction "2_2") (pintype "passive"))
      (node (ref "C6") (pin "2") (pinfunction "2_2") (pintype "passive"))
      (node (ref "C7") (pin "2") (pinfunction "2_2") (pintype "passive"))
      (node (ref "C8") (pin "2") (pinfunction "2_2") (pintype "passive"))
      (node (ref "C9") (pin "2") (pinfunction "2_2") (pintype "passive"))
      (node (ref "D1") (pin "1") (pinfunction "CATHODE_1") (pintype "passive"))
      (node (ref "D2") (pin "1") (pinfunction "CATHODE_1") (pintype "passive"))
      (node (ref "D3") (pin "1") (pinfunction "CATHODE_1") (pintype "passive"))
      (node (ref "J1") (pin "A1/B12") (pinfunction "GND_A1/B12") (pintype "power_in"))
      (node (ref "J1") (pin "B1/A12") (pinfunction "GND_B1/A12") (pintype "power_in"))
      (node (ref "J1") (pin "S1") (pinfunction "GND_S1") (pintype "power_in"))
      (node (ref "J1") (pin "S2") (pinfunction "GND_S2") (pintype "power_in"))
      (node (ref "J1") (pin "S3") (pinfunction "GND_S3") (pintype "power_in"))
      (node (ref "J1") (pin "S4") (pinfunction "GND_S4") (pintype "power_in"))
      (node (ref "J11") (pin "4") (pinfunction "4_4") (pintype "bidirectional"))
      (node (ref "J14") (pin "4") (pinfunction "4_4") (pintype "bidirectional"))
      (node (ref "J2") (pin "2") (pinfunction "2_2") (pintype "passive"))
      (node (ref "J5") (pin "4") (pinfunction "4_4") (pintype "bidirectional"))
      (node (ref "J8") (pin "4") (pinfunction "4_4") (pintype "bidirectional"))
      (node (ref "Q11") (pin "1") (pinfunction "S_1") (pintype "bidirectional"))
      (node (ref "Q5") (pin "1") (pinfunction "S_1") (pintype "bidirectional"))
      (node (ref "Q7") (pin "1") (pinfunction "S_1") (pintype "bidirectional"))
      (node (ref "Q9") (pin "1") (pinfunction "S_1") (pintype "bidirectional"))
      (node (ref "R1") (pin "1") (pinfunction "1_1") (pintype "passive"))
      (node (ref "R16") (pin "1") (pinfunction "1_1") (pintype "passive"))
      (node (ref "R2") (pin "1") (pinfunction "1_1") (pintype "passive"))
      (node (ref "R21") (pin "1") (pinfunction "1_1") (pintype "passive"))
      (node (ref "R28") (pin "2") (pinfunction "2_2") (pintype "passive"))
      (node (ref "R31") (pin "2") (pinfunction "2_2") (pintype "passive"))
      (node (ref "R34") (pin "2") (pinfunction "2_2") (pintype "passive"))
      (node (ref "R37") (pin "2") (pinfunction "2_2") (pintype "passive"))
      (node (ref "R5") (pin "2") (pinfunction "2_2") (pintype "passive"))
      (node (ref "R9") (pin "1") (pinfunction "1_1") (pintype "passive"))
      (node (ref "U1") (pin "2") (pinfunction "GND_2") (pintype "power_in"))
      (node (ref "U2") (pin "1") (pinfunction "GND_1") (pintype "passive"))
      (node (ref "U3") (pin "2") (pinfunction "GND_2") (pintype "power_in"))
      (node (ref "U3") (pin "25") (pinfunction "GND_25") (pintype "power_in"))
      (node (ref "U4") (pin "1") (pinfunction "GND_1") (pintype "power_in"))
      (node (ref "U4") (pin "15") (pinfunction "GND_15") (pintype "power_in"))
      (node (ref "U4") (pin "38") (pinfunction "GND_38") (pintype "power_in"))
      (node (ref "U4") (pin "39@1") (pinfunction "P_GND_39@1") (pintype "power_in"))
      (node (ref "U4") (pin "39@2") (pinfunction "P_GND_39@2") (pintype "power_in"))
      (node (ref "U4") (pin "39@3") (pinfunction "P_GND_39@3") (pintype "power_in"))
      (node (ref "U4") (pin "39@4") (pinfunction "P_GND_39@4") (pintype "power_in"))
      (node (ref "U4") (pin "39@5") (pinfunction "P_GND_39@5") (pintype "power_in"))
      (node (ref "U4") (pin "39@6") (pinfunction "P_GND_39@6") (pintype "power_in"))
      (node (ref "U4") (pin "39@7") (pinfunction "P_GND_39@7") (pintype "power_in"))
      (node (ref "U4") (pin "39@8") (pinfunction "P_GND_39@8") (pintype "power_in"))
      (node (ref "U4") (pin "39@9") (pinfunction "P_GND_39@9") (pintype "power_in"))
      (node (ref "U5") (pin "4") (pinfunction "EN2A_4") (pintype "input"))
      (node (ref "U5") (pin "5") (pinfunction "EN2B_5") (pintype "input"))
      (node (ref "U5") (pin "8") (pinfunction "GND_8") (pintype "power_in"))
      (node (ref "U6") (pin "7") (pinfunction "GND_7") (pintype "bidirectional"))
    )
    (net (code "69") (name "Net-(C3-Pad1)") (class "Default")
      (node (ref "C3") (pin "1") (pinfunction "1_1") (pintype "passive"))
      (node (ref "R5") (pin "1") (pinfunction "1_1") (pintype "passive"))
      (node (ref "R6") (pin "1") (pinfunction "1_1") (pintype "passive"))
      (node (ref "R7") (pin "2") (pinfunction "2_2") (pintype "passive"))
    )
    (net (code "70") (name "Net-(D4-PadC)") (class "Default")
      (node (ref "D4") (pin "C") (pinfunction "C_C") (pintype "passive"))
      (node (ref "Q1") (pin "S") (pinfunction "S_S") (pintype "bidirectional"))
      (node (ref "R3") (pin "1") (pinfunction "1_1") (pintype "passive"))
    )
    (net (code "71") (name "Net-(J1-CC1)") (class "Default")
      (node (ref "J1") (pin "A5") (pinfunction "CC1_A5") (pintype "bidirectional"))
      (node (ref "R1") (pin "2") (pinfunction "2_2") (pintype "passive"))
    )
    (net (code "72") (name "Net-(J1-CC2)") (class "Default")
      (node (ref "J1") (pin "B5") (pinfunction "CC2_B5") (pintype "bidirectional"))
      (node (ref "R2") (pin "2") (pinfunction "2_2") (pintype "passive"))
    )
    (net (code "73") (name "Net-(L1-2)") (class "Default")
      (node (ref "C2") (pin "2") (pinfunction "2_2") (pintype "passive"))
      (node (ref "L1") (pin "P$2") (pinfunction "2_P$2") (pintype "passive"))
      (node (ref "U1") (pin "3") (pinfunction "SW_3") (pintype "output"))
    )
    (net (code "74") (name "Net-(Q2-Pad1)") (class "Default")
      (node (ref "Q2") (pin "1") (pinfunction "1_1") (pintype "passive"))
      (node (ref "R14") (pin "2") (pinfunction "2_2") (pintype "passive"))
    )
    (net (code "75") (name "Net-(Q3-Pad1)") (class "Default")
      (node (ref "Q3") (pin "1") (pinfunction "1_1") (pintype "passive"))
      (node (ref "R15") (pin "2") (pinfunction "2_2") (pintype "passive"))
    )
    (net (code "76") (name "Net-(Q4A-D1)") (class "Default")
      (node (ref "Q4") (pin "6") (pinfunction "D1_6") (pintype "passive"))
      (node (ref "Q5") (pin "2") (pinfunction "G_2") (pintype "bidirectional"))
      (node (ref "R28") (pin "1") (pinfunction "1_1") (pintype "passive"))
    )
    (net (code "77") (name "Net-(Q5-D)") (class "Default")
      (node (ref "D5") (pin "A") (pinfunction "A_A") (pintype "passive"))
      (node (ref "J4") (pin "1") (pinfunction "1_1") (pintype "passive"))
      (node (ref "J4") (pin "2") (pinfunction "1_2") (pintype "passive"))
      (node (ref "Q5") (pin "3") (pinfunction "D_3") (pintype "bidirectional"))
    )
    (net (code "78") (name "Net-(Q6A-D1)") (class "Default")
      (node (ref "Q6") (pin "6") (pinfunction "D1_6") (pintype "passive"))
      (node (ref "Q7") (pin "2") (pinfunction "G_2") (pintype "bidirectional"))
      (node (ref "R31") (pin "1") (pinfunction "1_1") (pintype "passive"))
    )
    (net (code "79") (name "Net-(Q7-D)") (class "Default")
      (node (ref "D6") (pin "A") (pinfunction "A_A") (pintype "passive"))
      (node (ref "J7") (pin "1") (pinfunction "1_1") (pintype "passive"))
      (node (ref "J7") (pin "2") (pinfunction "1_2") (pintype "passive"))
      (node (ref "Q7") (pin "3") (pinfunction "D_3") (pintype "bidirectional"))
    )
    (net (code "80") (name "Net-(Q8A-D1)") (class "Default")
      (node (ref "Q8") (pin "6") (pinfunction "D1_6") (pintype "passive"))
      (node (ref "Q9") (pin "2") (pinfunction "G_2") (pintype "bidirectional"))
      (node (ref "R34") (pin "1") (pinfunction "1_1") (pintype "passive"))
    )
    (net (code "81") (name "Net-(Q9-D)") (class "Default")
      (node (ref "D7") (pin "A") (pinfunction "A_A") (pintype "passive"))
      (node (ref "J10") (pin "1") (pinfunction "1_1") (pintype "passive"))
      (node (ref "J10") (pin "2") (pinfunction "1_2") (pintype "passive"))
      (node (ref "Q9") (pin "3") (pinfunction "D_3") (pintype "bidirectional"))
    )
    (net (code "82") (name "Net-(Q10A-D1)") (class "Default")
      (node (ref "Q10") (pin "6") (pinfunction "D1_6") (pintype "passive"))
      (node (ref "Q11") (pin "2") (pinfunction "G_2") (pintype "bidirectional"))
      (node (ref "R37") (pin "1") (pinfunction "1_1") (pintype "passive"))
    )
    (net (code "83") (name "Net-(Q11-D)") (class "Default")
      (node (ref "D8") (pin "A") (pinfunction "A_A") (pintype "passive"))
      (node (ref "J13") (pin "1") (pinfunction "1_1") (pintype "passive"))
      (node (ref "J13") (pin "2") (pinfunction "1_2") (pintype "passive"))
      (node (ref "Q11") (pin "3") (pinfunction "D_3") (pintype "bidirectional"))
    )
    (net (code "84") (name "Net-(U1-BST)") (class "Default")
      (node (ref "C2") (pin "1") (pinfunction "1_1") (pintype "passive"))
      (node (ref "U1") (pin "4") (pinfunction "BST_4") (pintype "input"))
    )
    (net (code "85") (name "Net-(U1-EN)") (class "Default")
      (node (ref "R4") (pin "2") (pinfunction "2_2") (pintype "passive"))
      (node (ref "U1") (pin "5") (pinfunction "EN_5") (pintype "input"))
    )
    (net (code "86") (name "Net-(U1-FB)") (class "Default")
      (node (ref "R6") (pin "2") (pinfunction "2_2") (pintype "passive"))
      (node (ref "U1") (pin "6") (pinfunction "FB_6") (pintype "input"))
    )
    (net (code "87") (name "Net-(U3-VBUS)") (class "Default")
      (node (ref "R8") (pin "1") (pinfunction "1_1") (pintype "passive"))
      (node (ref "R9") (pin "2") (pinfunction "2_2") (pintype "passive"))
      (node (ref "U3") (pin "8") (pinfunction "VBUS_8") (pintype "input"))
    )
    (net (code "88") (name "Net-(U3-~{RST})") (class "Default")
      (node (ref "R10") (pin "1") (pinfunction "1_1") (pintype "passive"))
      (node (ref "U3") (pin "9") (pinfunction "~{RST}_9") (pintype "bidirectional"))
    )
    (net (code "89") (name "unconnected-(J1-SBU1-PadA8)") (class "Default")
      (node (ref "J1") (pin "A8") (pinfunction "SBU1_A8") (pintype "bidirectional"))
    )
    (net (code "90") (name "unconnected-(J1-SBU2-PadB8)") (class "Default")
      (node (ref "J1") (pin "B8") (pinfunction "SBU2_B8") (pintype "bidirectional"))
    )
    (net (code "91") (name "unconnected-(U3-GPIO.0{slash}TXT-Pad14)") (class "Default")
      (node (ref "U3") (pin "14") (pinfunction "GPIO.0/TXT_14") (pintype "bidirectional"))
    )
    (net (code "92") (name "unconnected-(U3-GPIO.1{slash}RXT-Pad13)") (class "Default")
      (node (ref "U3") (pin "13") (pinfunction "GPIO.1/RXT_13") (pintype "bidirectional"))
    )
    (net (code "93") (name "unconnected-(U3-GPIO.2{slash}RS485-Pad12)") (class "Default")
      (node (ref "U3") (pin "12") (pinfunction "GPIO.2/RS485_12") (pintype "bidirectional"))
    )
    (net (code "94") (name "unconnected-(U3-GPIO.3{slash}WAKEUP-Pad11)") (class "Default")
      (node (ref "U3") (pin "11") (pinfunction "GPIO.3/WAKEUP_11") (pintype "bidirectional"))
    )
    (net (code "95") (name "unconnected-(U3-NC-Pad10)") (class "Default")
      (node (ref "U3") (pin "10") (pinfunction "NC_10") (pintype "no_connect"))
    )
    (net (code "96") (name "unconnected-(U3-NC-Pad16)") (class "Default")
      (node (ref "U3") (pin "16") (pinfunction "NC_16") (pintype "no_connect"))
    )
    (net (code "97") (name "unconnected-(U3-SUSPEND-Pad17)") (class "Default")
      (node (ref "U3") (pin "17") (pinfunction "SUSPEND_17") (pintype "output"))
    )
    (net (code "98") (name "unconnected-(U4-NC-Pad17)") (class "Default")
      (node (ref "U4") (pin "17") (pinfunction "NC_17") (pintype "no_connect"))
    )
    (net (code "99") (name "unconnected-(U4-NC-Pad18)") (class "Default")
      (node (ref "U4") (pin "18") (pinfunction "NC_18") (pintype "no_connect"))
    )
    (net (code "100") (name "unconnected-(U4-NC-Pad19)") (class "Default")
      (node (ref "U4") (pin "19") (pinfunction "NC_19") (pintype "no_connect"))
    )
    (net (code "101") (name "unconnected-(U4-NC-Pad20)") (class "Default")
      (node (ref "U4") (pin "20") (pinfunction "NC_20") (pintype "no_connect"))
    )
    (net (code "102") (name "unconnected-(U4-NC-Pad21)") (class "Default")
      (node (ref "U4") (pin "21") (pinfunction "NC_21") (pintype "no_connect"))
    )
    (net (code "103") (name "unconnected-(U4-NC-Pad22)") (class "Default")
      (node (ref "U4") (pin "22") (pinfunction "NC_22") (pintype "no_connect"))
    )
    (net (code "104") (name "unconnected-(U4-NC-Pad32)") (class "Default")
      (node (ref "U4") (pin "32") (pinfunction "NC_32") (pintype "no_connect"))
    )
  )
)
